# Sedra.net
KiCad netlist of a schematic drawn in Altium Designer
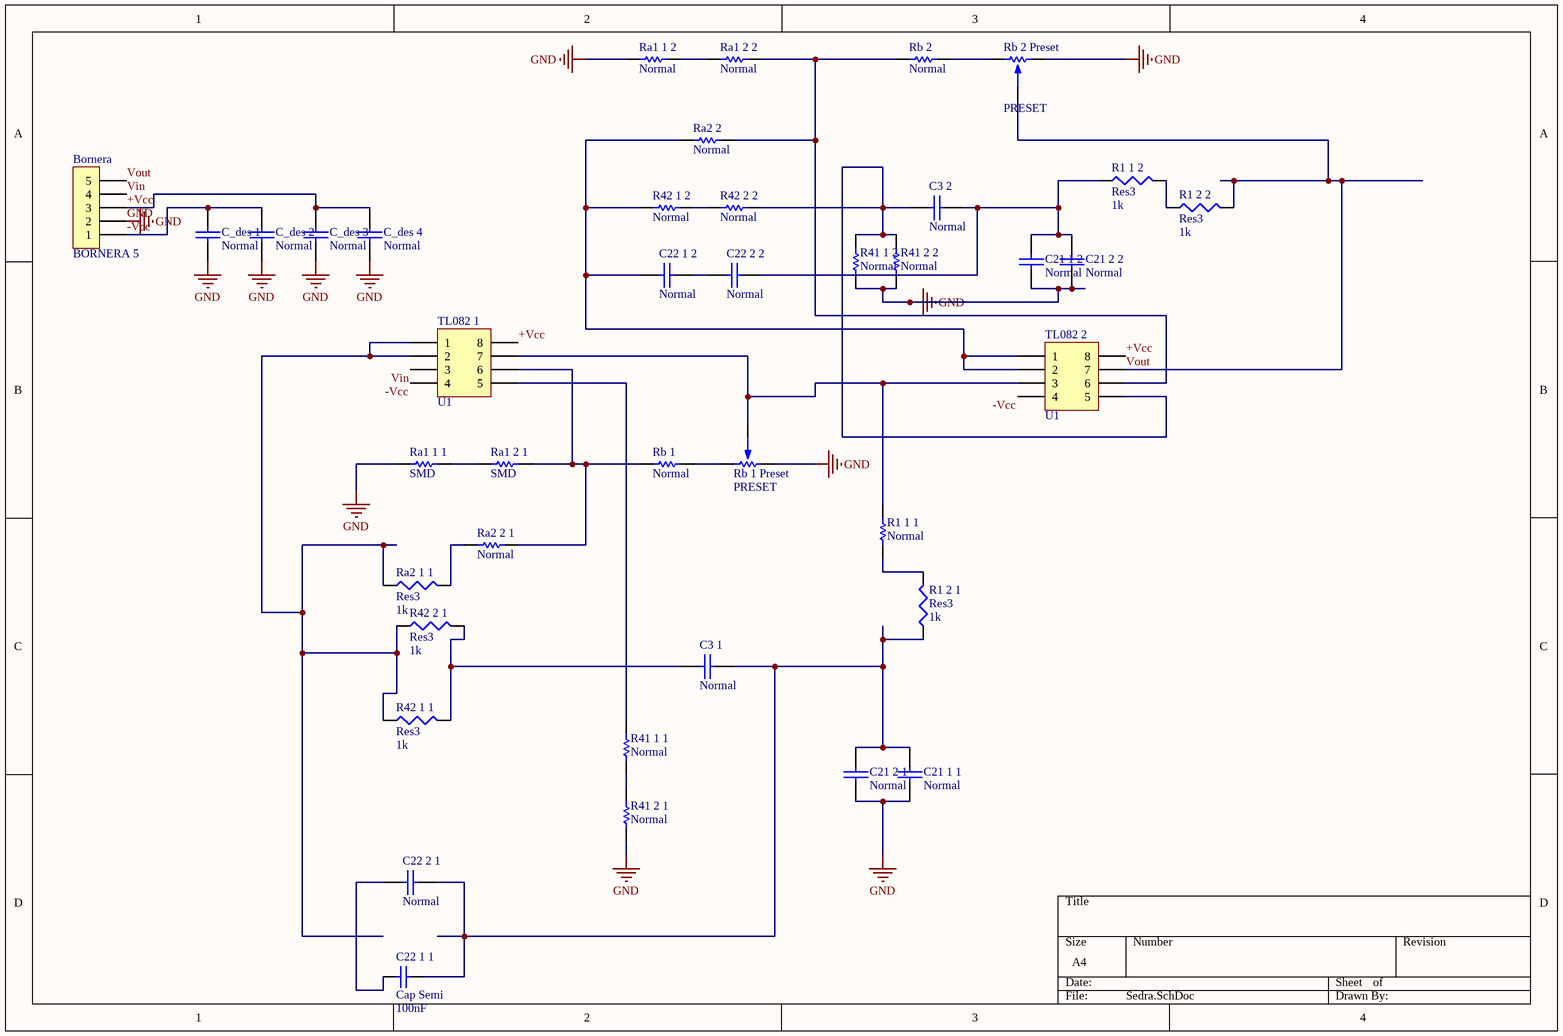
[diagram p0: Sedra.SchDoc]

(export (version "E")
  (design (tool "Eeschema 10.0.6"))
  (components
    (comp (ref "Bornera")
      (value "BORNERA 5")
      (footprint "BORNERA5")
      (libsource (lib "LIBEBAL") (part "BORNERA 5"))
    )
    (comp (ref "C3 1") (value "Normal") (footprint "CAP200") (libsource (lib "LIBEBAL") (part "CAP")))
    (comp (ref "C3 2") (value "Normal") (footprint "CAP200") (libsource (lib "LIBEBAL") (part "CAP")))
    (comp (ref "C21 1 1") (value "Normal") (footprint "CAP200") (libsource (lib "LIBEBAL") (part "CAP")))
    (comp (ref "C21 1 2") (value "Normal") (footprint "CAP200") (libsource (lib "LIBEBAL") (part "CAP")))
    (comp (ref "C21 2 1") (value "Normal") (footprint "CAP200") (libsource (lib "LIBEBAL") (part "CAP")))
    (comp (ref "C21 2 2") (value "Normal") (footprint "CAP200") (libsource (lib "LIBEBAL") (part "CAP")))
    (comp (ref "C22 1 1")
      (value "Cap Semi")
      (footprint "C1210")
      (description "Capacitor (Semiconductor SIM Model)")
      (fields (field (name "ALTIUM_VALUE") "100nF") (field (name "PUBLISHER") "Altium Limited"))
      (libsource (lib "Miscellaneous Devices") (part "Cap Semi"))
    )
    (comp (ref "C22 1 2") (value "Normal") (footprint "CAP200") (libsource (lib "LIBEBAL") (part "CAP")))
    (comp (ref "C22 2 1") (value "Normal") (footprint "CAP200") (libsource (lib "LIBEBAL") (part "CAP")))
    (comp (ref "C22 2 2") (value "Normal") (footprint "CAP200") (libsource (lib "LIBEBAL") (part "CAP")))
    (comp (ref "C_des 1") (value "Normal") (footprint "CAP200") (libsource (lib "LIBEBAL") (part "CAP")))
    (comp (ref "C_des 2") (value "Normal") (footprint "CAP200") (libsource (lib "LIBEBAL") (part "CAP")))
    (comp (ref "C_des 3") (value "Normal") (footprint "CAP200") (libsource (lib "LIBEBAL") (part "CAP")))
    (comp (ref "C_des 4") (value "Normal") (footprint "CAP200") (libsource (lib "LIBEBAL") (part "CAP")))
    (comp (ref "R1 1 1") (value "Normal") (footprint "RES400") (libsource (lib "LIBEBAL") (part "RES")))
    (comp (ref "R1 1 2")
      (value "Res3")
      (footprint "6-0805_M")
      (description "Resistor")
      (fields (field (name "ALTIUM_VALUE") "1k") (field (name "PUBLISHER") "Altium Limited"))
      (libsource (lib "Miscellaneous Devices") (part "Res3"))
    )
    (comp (ref "R1 2 1")
      (value "Res3")
      (footprint "6-0805_M")
      (description "Resistor")
      (fields (field (name "ALTIUM_VALUE") "1k") (field (name "PUBLISHER") "Altium Limited"))
      (libsource (lib "Miscellaneous Devices") (part "Res3"))
    )
    (comp (ref "R1 2 2")
      (value "Res3")
      (footprint "6-0805_M")
      (description "Resistor")
      (fields (field (name "ALTIUM_VALUE") "1k") (field (name "PUBLISHER") "Altium Limited"))
      (libsource (lib "Miscellaneous Devices") (part "Res3"))
    )
    (comp (ref "R41 1 1") (value "Normal") (footprint "RES400") (libsource (lib "LIBEBAL") (part "RES")))
    (comp (ref "R41 1 2") (value "Normal") (footprint "RES400") (libsource (lib "LIBEBAL") (part "RES")))
    (comp (ref "R41 2 1") (value "Normal") (footprint "RES400") (libsource (lib "LIBEBAL") (part "RES")))
    (comp (ref "R41 2 2") (value "Normal") (footprint "RES400") (libsource (lib "LIBEBAL") (part "RES")))
    (comp (ref "R42 1 1")
      (value "Res3")
      (footprint "6-0805_M")
      (description "Resistor")
      (fields (field (name "ALTIUM_VALUE") "1k") (field (name "PUBLISHER") "Altium Limited"))
      (libsource (lib "Miscellaneous Devices") (part "Res3"))
    )
    (comp (ref "R42 1 2") (value "Normal") (footprint "RES400") (libsource (lib "LIBEBAL") (part "RES")))
    (comp (ref "R42 2 1")
      (value "Res3")
      (footprint "6-0805_M")
      (description "Resistor")
      (fields (field (name "ALTIUM_VALUE") "1k") (field (name "PUBLISHER") "Altium Limited"))
      (libsource (lib "Miscellaneous Devices") (part "Res3"))
    )
    (comp (ref "R42 2 2") (value "Normal") (footprint "RES400") (libsource (lib "LIBEBAL") (part "RES")))
    (comp (ref "Ra1 1 1") (value "SMD") (footprint "0805") (libsource (lib "LIBEBAL") (part "RES")))
    (comp (ref "Ra1 1 2") (value "Normal") (footprint "RES400") (libsource (lib "LIBEBAL") (part "RES")))
    (comp (ref "Ra1 2 1") (value "SMD") (footprint "0805") (libsource (lib "LIBEBAL") (part "RES")))
    (comp (ref "Ra1 2 2") (value "Normal") (footprint "RES400") (libsource (lib "LIBEBAL") (part "RES")))
    (comp (ref "Ra2 1 1")
      (value "Res3")
      (footprint "6-0805_M")
      (description "Resistor")
      (fields (field (name "ALTIUM_VALUE") "1k") (field (name "PUBLISHER") "Altium Limited"))
      (libsource (lib "Miscellaneous Devices") (part "Res3"))
    )
    (comp (ref "Ra2 2") (value "Normal") (footprint "RES400") (libsource (lib "LIBEBAL") (part "RES")))
    (comp (ref "Ra2 2 1") (value "Normal") (footprint "RES400") (libsource (lib "LIBEBAL") (part "RES")))
    (comp (ref "Rb 1") (value "Normal") (footprint "RES400") (libsource (lib "LIBEBAL") (part "RES")))
    (comp (ref "Rb 1 Preset")
      (value "PRESET")
      (footprint "PRESET V")
      (libsource (lib "LIBEBAL") (part "PRESET"))
    )
    (comp (ref "Rb 2") (value "Normal") (footprint "RES400") (libsource (lib "LIBEBAL") (part "RES")))
    (comp (ref "Rb 2 Preset")
      (value "PRESET")
      (footprint "PRESET V")
      (libsource (lib "LIBEBAL") (part "PRESET"))
    )
    (comp (ref "TL082 1") (value "U1") (footprint "DIP8") (libsource (lib "LIBEBAL") (part "IC_DIP8")))
    (comp (ref "TL082 2") (value "U1") (footprint "DIP8") (libsource (lib "LIBEBAL") (part "IC_DIP8")))
  )
  (nets
    (net (code "1") (name "/+Vcc") (class "Default")
      (node (ref "Bornera") (pin "3") (pinfunction "3_3") (pintype "passive"))
      (node (ref "C_des 3") (pin "2") (pinfunction "2_2") (pintype "passive"))
      (node (ref "C_des 4") (pin "2") (pinfunction "2_2") (pintype "passive"))
      (node (ref "TL082 1") (pin "8") (pinfunction "8_8") (pintype "passive"))
      (node (ref "TL082 2") (pin "8") (pinfunction "8_8") (pintype "passive"))
    )
    (net (code "2") (name "/-Vcc") (class "Default")
      (node (ref "Bornera") (pin "1") (pinfunction "1_1") (pintype "passive"))
      (node (ref "C_des 1") (pin "2") (pinfunction "2_2") (pintype "passive"))
      (node (ref "C_des 2") (pin "2") (pinfunction "2_2") (pintype "passive"))
      (node (ref "TL082 1") (pin "4") (pinfunction "4_4") (pintype "passive"))
      (node (ref "TL082 2") (pin "4") (pinfunction "4_4") (pintype "passive"))
    )
    (net (code "3") (name "/Vin") (class "Default")
      (node (ref "Bornera") (pin "4") (pinfunction "4_4") (pintype "passive"))
      (node (ref "TL082 1") (pin "3") (pinfunction "3_3") (pintype "passive"))
    )
    (net (code "4") (name "/Vout") (class "Default")
      (node (ref "Bornera") (pin "5") (pinfunction "5_5") (pintype "passive"))
      (node (ref "R1 2 2") (pin "2") (pinfunction "2_2") (pintype "passive"))
      (node (ref "Rb 2 Preset") (pin "2") (pinfunction "2_2") (pintype "passive"))
      (node (ref "TL082 2") (pin "7") (pinfunction "7_7") (pintype "passive"))
    )
    (net (code "5") (name "GND") (class "Default")
      (node (ref "Bornera") (pin "2") (pinfunction "2_2") (pintype "passive"))
      (node (ref "C21 1 1") (pin "1") (pinfunction "1_1") (pintype "passive"))
      (node (ref "C21 1 2") (pin "1") (pinfunction "1_1") (pintype "passive"))
      (node (ref "C21 2 1") (pin "1") (pinfunction "1_1") (pintype "passive"))
      (node (ref "C21 2 2") (pin "1") (pinfunction "1_1") (pintype "passive"))
      (node (ref "C_des 1") (pin "1") (pinfunction "1_1") (pintype "passive"))
      (node (ref "C_des 2") (pin "1") (pinfunction "1_1") (pintype "passive"))
      (node (ref "C_des 3") (pin "1") (pinfunction "1_1") (pintype "passive"))
      (node (ref "C_des 4") (pin "1") (pinfunction "1_1") (pintype "passive"))
      (node (ref "R41 1 2") (pin "1") (pinfunction "1_1") (pintype "passive"))
      (node (ref "R41 2 1") (pin "1") (pinfunction "1_1") (pintype "passive"))
      (node (ref "R41 2 2") (pin "1") (pinfunction "1_1") (pintype "passive"))
      (node (ref "Ra1 1 1") (pin "1") (pinfunction "1_1") (pintype "passive"))
      (node (ref "Ra1 1 2") (pin "1") (pinfunction "1_1") (pintype "passive"))
      (node (ref "Rb 1 Preset") (pin "3") (pinfunction "3_3") (pintype "passive"))
      (node (ref "Rb 2 Preset") (pin "1") (pinfunction "1_1") (pintype "passive"))
    )
    (net (code "6") (name "Net-(C3 1-Pad1)") (class "Default")
      (node (ref "C3 1") (pin "1") (pinfunction "1_1") (pintype "passive"))
      (node (ref "R42 1 1") (pin "2") (pinfunction "2_2") (pintype "passive"))
      (node (ref "R42 2 1") (pin "2") (pinfunction "2_2") (pintype "passive"))
    )
    (net (code "7") (name "Net-(C3 2-Pad1)") (class "Default")
      (node (ref "C3 2") (pin "1") (pinfunction "1_1") (pintype "passive"))
      (node (ref "R41 1 2") (pin "2") (pinfunction "2_2") (pintype "passive"))
      (node (ref "R41 2 2") (pin "2") (pinfunction "2_2") (pintype "passive"))
      (node (ref "R42 2 2") (pin "2") (pinfunction "2_2") (pintype "passive"))
      (node (ref "TL082 2") (pin "5") (pinfunction "5_5") (pintype "passive"))
    )
    (net (code "8") (name "Net-(C21 1 1-Pad2)") (class "Default")
      (node (ref "C21 1 1") (pin "2") (pinfunction "2_2") (pintype "passive"))
      (node (ref "C21 2 1") (pin "2") (pinfunction "2_2") (pintype "passive"))
      (node (ref "C22 1 1") (pin "1") (pinfunction "1_1") (pintype "passive"))
      (node (ref "C22 2 1") (pin "2") (pinfunction "2_2") (pintype "passive"))
      (node (ref "C3 1") (pin "2") (pinfunction "2_2") (pintype "passive"))
      (node (ref "R1 2 1") (pin "1") (pinfunction "1_1") (pintype "passive"))
    )
    (net (code "9") (name "Net-(C21 1 2-Pad2)") (class "Default")
      (node (ref "C21 1 2") (pin "2") (pinfunction "2_2") (pintype "passive"))
      (node (ref "C21 2 2") (pin "2") (pinfunction "2_2") (pintype "passive"))
      (node (ref "C22 2 2") (pin "2") (pinfunction "2_2") (pintype "passive"))
      (node (ref "C3 2") (pin "2") (pinfunction "2_2") (pintype "passive"))
      (node (ref "R1 1 2") (pin "1") (pinfunction "1_1") (pintype "passive"))
    )
    (net (code "10") (name "Net-(C22 1 1-Pad2)") (class "Default")
      (node (ref "C22 1 1") (pin "2") (pinfunction "2_2") (pintype "passive"))
      (node (ref "C22 2 1") (pin "1") (pinfunction "1_1") (pintype "passive"))
    )
    (net (code "11") (name "Net-(C22 1 2-Pad1)") (class "Default")
      (node (ref "C22 1 2") (pin "1") (pinfunction "1_1") (pintype "passive"))
      (node (ref "R42 1 2") (pin "1") (pinfunction "1_1") (pintype "passive"))
      (node (ref "Ra2 2") (pin "1") (pinfunction "1_1") (pintype "passive"))
      (node (ref "TL082 2") (pin "1") (pinfunction "1_1") (pintype "passive"))
      (node (ref "TL082 2") (pin "2") (pinfunction "2_2") (pintype "passive"))
    )
    (net (code "12") (name "Net-(C22 1 2-Pad2)") (class "Default")
      (node (ref "C22 1 2") (pin "2") (pinfunction "2_2") (pintype "passive"))
      (node (ref "C22 2 2") (pin "1") (pinfunction "1_1") (pintype "passive"))
    )
    (net (code "13") (name "Net-(R1 1 1-Pad1)") (class "Default")
      (node (ref "R1 1 1") (pin "1") (pinfunction "1_1") (pintype "passive"))
      (node (ref "R1 2 1") (pin "2") (pinfunction "2_2") (pintype "passive"))
    )
    (net (code "14") (name "Net-(R1 1 1-Pad2)") (class "Default")
      (node (ref "R1 1 1") (pin "2") (pinfunction "2_2") (pintype "passive"))
      (node (ref "Rb 1 Preset") (pin "2") (pinfunction "2_2") (pintype "passive"))
      (node (ref "TL082 1") (pin "7") (pinfunction "7_7") (pintype "passive"))
      (node (ref "TL082 2") (pin "3") (pinfunction "3_3") (pintype "passive"))
    )
    (net (code "15") (name "Net-(R1 1 2-Pad2)") (class "Default")
      (node (ref "R1 1 2") (pin "2") (pinfunction "2_2") (pintype "passive"))
      (node (ref "R1 2 2") (pin "1") (pinfunction "1_1") (pintype "passive"))
    )
    (net (code "16") (name "Net-(R41 1 1-Pad1)") (class "Default")
      (node (ref "R41 1 1") (pin "1") (pinfunction "1_1") (pintype "passive"))
      (node (ref "R41 2 1") (pin "2") (pinfunction "2_2") (pintype "passive"))
    )
    (net (code "17") (name "Net-(R41 1 1-Pad2)") (class "Default")
      (node (ref "R41 1 1") (pin "2") (pinfunction "2_2") (pintype "passive"))
      (node (ref "TL082 1") (pin "5") (pinfunction "5_5") (pintype "passive"))
    )
    (net (code "18") (name "Net-(R42 1 1-Pad1)") (class "Default")
      (node (ref "R42 1 1") (pin "1") (pinfunction "1_1") (pintype "passive"))
      (node (ref "R42 2 1") (pin "1") (pinfunction "1_1") (pintype "passive"))
      (node (ref "Ra2 1 1") (pin "1") (pinfunction "1_1") (pintype "passive"))
      (node (ref "TL082 1") (pin "1") (pinfunction "1_1") (pintype "passive"))
      (node (ref "TL082 1") (pin "2") (pinfunction "2_2") (pintype "passive"))
    )
    (net (code "19") (name "Net-(R42 1 2-Pad2)") (class "Default")
      (node (ref "R42 1 2") (pin "2") (pinfunction "2_2") (pintype "passive"))
      (node (ref "R42 2 2") (pin "1") (pinfunction "1_1") (pintype "passive"))
    )
    (net (code "20") (name "Net-(Ra1 1 1-Pad2)") (class "Default")
      (node (ref "Ra1 1 1") (pin "2") (pinfunction "2_2") (pintype "passive"))
      (node (ref "Ra1 2 1") (pin "1") (pinfunction "1_1") (pintype "passive"))
    )
    (net (code "21") (name "Net-(Ra1 1 2-Pad2)") (class "Default")
      (node (ref "Ra1 1 2") (pin "2") (pinfunction "2_2") (pintype "passive"))
      (node (ref "Ra1 2 2") (pin "1") (pinfunction "1_1") (pintype "passive"))
    )
    (net (code "22") (name "Net-(Ra1 2 1-Pad2)") (class "Default")
      (node (ref "Ra1 2 1") (pin "2") (pinfunction "2_2") (pintype "passive"))
      (node (ref "Ra2 2 1") (pin "2") (pinfunction "2_2") (pintype "passive"))
      (node (ref "Rb 1") (pin "1") (pinfunction "1_1") (pintype "passive"))
      (node (ref "TL082 1") (pin "6") (pinfunction "6_6") (pintype "passive"))
    )
    (net (code "23") (name "Net-(Ra1 2 2-Pad2)") (class "Default")
      (node (ref "Ra1 2 2") (pin "2") (pinfunction "2_2") (pintype "passive"))
      (node (ref "Ra2 2") (pin "2") (pinfunction "2_2") (pintype "passive"))
      (node (ref "Rb 2") (pin "1") (pinfunction "1_1") (pintype "passive"))
      (node (ref "TL082 2") (pin "6") (pinfunction "6_6") (pintype "passive"))
    )
    (net (code "24") (name "Net-(Ra2 1 1-Pad2)") (class "Default")
      (node (ref "Ra2 1 1") (pin "2") (pinfunction "2_2") (pintype "passive"))
      (node (ref "Ra2 2 1") (pin "1") (pinfunction "1_1") (pintype "passive"))
    )
    (net (code "25") (name "Net-(Rb 1 Preset-Pad1)") (class "Default")
      (node (ref "Rb 1") (pin "2") (pinfunction "2_2") (pintype "passive"))
      (node (ref "Rb 1 Preset") (pin "1") (pinfunction "1_1") (pintype "passive"))
    )
    (net (code "26") (name "Net-(Rb 2 Preset-Pad3)") (class "Default")
      (node (ref "Rb 2") (pin "2") (pinfunction "2_2") (pintype "passive"))
      (node (ref "Rb 2 Preset") (pin "3") (pinfunction "3_3") (pintype "passive"))
    )
  )
)
